# R_P.net
KiCad netlist of a schematic drawn in EAGLE
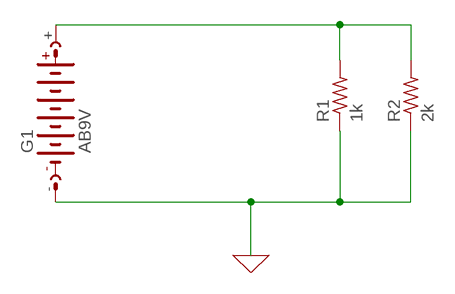
[diagram p0: schematic, sheet 1]

(export (version "E")
  (design (tool "Eeschema 10.0.6"))
  (components
    (comp (ref "G1")
      (value "AB9V")
      (footprint "eagle-import:AB9V")
      (libsource (lib "eagle-import") (part "AB9V"))
    )
    (comp (ref "R1")
      (value "1k")
      (footprint "eagle-import:0204V")
      (libsource (lib "eagle-import") (part "R-US_0204/2V"))
    )
    (comp (ref "R2")
      (value "2k")
      (footprint "eagle-import:0204V")
      (libsource (lib "eagle-import") (part "R-US_0204/2V"))
    )
  )
  (nets
    (net (code "1") (name "GND") (class "Default")
      (node (ref "G1") (pin "-") (pinfunction "-_-") (pintype "passive"))
      (node (ref "R1") (pin "1") (pinfunction "1_1") (pintype "passive"))
      (node (ref "R2") (pin "1") (pinfunction "1_1") (pintype "passive"))
    )
    (net (code "2") (name "Net-(G1-Pad+)") (class "Default")
      (node (ref "G1") (pin "+") (pinfunction "+_+") (pintype "passive"))
      (node (ref "R1") (pin "2") (pinfunction "2_2") (pintype "passive"))
      (node (ref "R2") (pin "2") (pinfunction "2_2") (pintype "passive"))
    )
  )
)
